# Header.net
KiCad netlist of a schematic drawn in Altium Designer
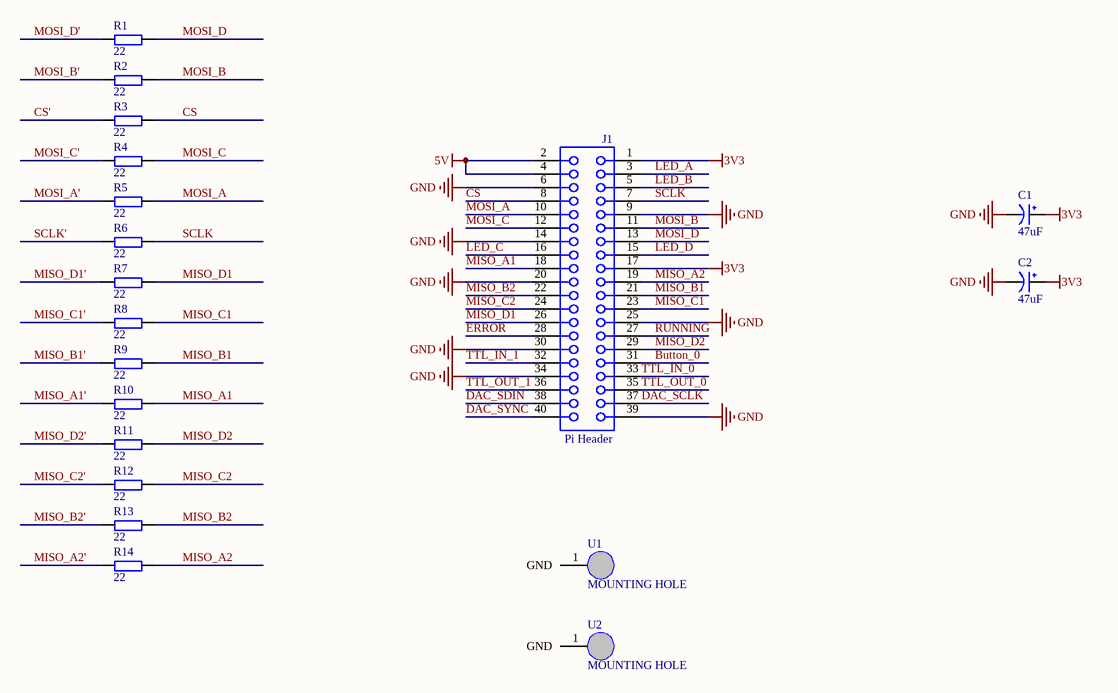
[diagram p0: Header.SchDoc]

(export (version "E")
  (design (tool "Eeschema 10.0.6"))
  (components
    (comp (ref "C1") (value "47uF") (footprint "CD A(3216)") (libsource (lib "ZYNQ_开发板") (part "CAP")))
    (comp (ref "C2") (value "47uF") (footprint "CD A(3216)") (libsource (lib "ZYNQ_开发板") (part "CAP")))
    (comp (ref "J1")
      (value "Pi Header")
      (footprint "61304021821")
      (description "THT Vertical Socket Header WR-PHD, Pitch 2.54 mm, Dual Row, 40 pins")
      (libsource (lib "Altium Content Vault") (part "Header_Female_2R_40P"))
    )
    (comp (ref "R1") (value "22") (footprint "R 0402_L") (libsource (lib "ZYNQ_开发板") (part "R")))
    (comp (ref "R2") (value "22") (footprint "R 0402_L") (libsource (lib "ZYNQ_开发板") (part "R")))
    (comp (ref "R3") (value "22") (footprint "R 0402_L") (libsource (lib "ZYNQ_开发板") (part "R")))
    (comp (ref "R4") (value "22") (footprint "R 0402_L") (libsource (lib "ZYNQ_开发板") (part "R")))
    (comp (ref "R5") (value "22") (footprint "R 0402_L") (libsource (lib "ZYNQ_开发板") (part "R")))
    (comp (ref "R6") (value "22") (footprint "R 0402_L") (libsource (lib "ZYNQ_开发板") (part "R")))
    (comp (ref "R7") (value "22") (footprint "R 0402_L") (libsource (lib "ZYNQ_开发板") (part "R")))
    (comp (ref "R8") (value "22") (footprint "R 0402_L") (libsource (lib "ZYNQ_开发板") (part "R")))
    (comp (ref "R9") (value "22") (footprint "R 0402_L") (libsource (lib "ZYNQ_开发板") (part "R")))
    (comp (ref "R10") (value "22") (footprint "R 0402_L") (libsource (lib "ZYNQ_开发板") (part "R")))
    (comp (ref "R11") (value "22") (footprint "R 0402_L") (libsource (lib "ZYNQ_开发板") (part "R")))
    (comp (ref "R12") (value "22") (footprint "R 0402_L") (libsource (lib "ZYNQ_开发板") (part "R")))
    (comp (ref "R13") (value "22") (footprint "R 0402_L") (libsource (lib "ZYNQ_开发板") (part "R")))
    (comp (ref "R14") (value "22") (footprint "R 0402_L") (libsource (lib "ZYNQ_开发板") (part "R")))
    (comp (ref "U1")
      (value "MOUNTING HOLE")
      (footprint "mounting_hole")
      (fields (field (name "PART NUMBER") "VJ0805Y105KXQRW1BC") (field (name "MANUFACTURER") "Vitramon"))
      (libsource (lib "Mounting_Hole") (part "MountingHole"))
    )
    (comp (ref "U2")
      (value "MOUNTING HOLE")
      (footprint "mounting_hole")
      (fields (field (name "PART NUMBER") "VJ0805Y105KXQRW1BC") (field (name "MANUFACTURER") "Vitramon"))
      (libsource (lib "Mounting_Hole") (part "MountingHole"))
    )
  )
  (nets
    (net (code "1") (name "/Button_0") (class "Default")
      (node (ref "J1") (pin "31") (pinfunction "31_31") (pintype "passive"))
    )
    (net (code "2") (name "/CS") (class "Default")
      (node (ref "J1") (pin "8") (pinfunction "8_8") (pintype "passive"))
      (node (ref "R3") (pin "2") (pintype "passive"))
    )
    (net (code "3") (name "/CS'") (class "Default") (node (ref "R3") (pin "1") (pintype "passive")))
    (net (code "4") (name "/DAC_SCLK") (class "Default")
      (node (ref "J1") (pin "37") (pinfunction "37_37") (pintype "passive"))
    )
    (net (code "5") (name "/DAC_SDIN") (class "Default")
      (node (ref "J1") (pin "38") (pinfunction "38_38") (pintype "passive"))
    )
    (net (code "6") (name "/DAC_SYNC") (class "Default")
      (node (ref "J1") (pin "40") (pinfunction "40_40") (pintype "passive"))
    )
    (net (code "7") (name "/ERROR") (class "Default")
      (node (ref "J1") (pin "28") (pinfunction "28_28") (pintype "passive"))
    )
    (net (code "8") (name "/LED_A") (class "Default")
      (node (ref "J1") (pin "3") (pinfunction "3_3") (pintype "passive"))
    )
    (net (code "9") (name "/LED_B") (class "Default")
      (node (ref "J1") (pin "5") (pinfunction "5_5") (pintype "passive"))
    )
    (net (code "10") (name "/LED_C") (class "Default")
      (node (ref "J1") (pin "16") (pinfunction "16_16") (pintype "passive"))
    )
    (net (code "11") (name "/LED_D") (class "Default")
      (node (ref "J1") (pin "15") (pinfunction "15_15") (pintype "passive"))
    )
    (net (code "12") (name "/MISO_A1") (class "Default")
      (node (ref "J1") (pin "18") (pinfunction "18_18") (pintype "passive"))
      (node (ref "R10") (pin "2") (pintype "passive"))
    )
    (net (code "13") (name "/MISO_A1'") (class "Default") (node (ref "R10") (pin "1") (pintype "passive")))
    (net (code "14") (name "/MISO_A2") (class "Default")
      (node (ref "J1") (pin "19") (pinfunction "19_19") (pintype "passive"))
      (node (ref "R14") (pin "2") (pintype "passive"))
    )
    (net (code "15") (name "/MISO_A2'") (class "Default") (node (ref "R14") (pin "1") (pintype "passive")))
    (net (code "16") (name "/MISO_B1") (class "Default")
      (node (ref "J1") (pin "21") (pinfunction "21_21") (pintype "passive"))
      (node (ref "R9") (pin "2") (pintype "passive"))
    )
    (net (code "17") (name "/MISO_B1'") (class "Default") (node (ref "R9") (pin "1") (pintype "passive")))
    (net (code "18") (name "/MISO_B2") (class "Default")
      (node (ref "J1") (pin "22") (pinfunction "22_22") (pintype "passive"))
      (node (ref "R13") (pin "2") (pintype "passive"))
    )
    (net (code "19") (name "/MISO_B2'") (class "Default") (node (ref "R13") (pin "1") (pintype "passive")))
    (net (code "20") (name "/MISO_C1") (class "Default")
      (node (ref "J1") (pin "23") (pinfunction "23_23") (pintype "passive"))
      (node (ref "R8") (pin "2") (pintype "passive"))
    )
    (net (code "21") (name "/MISO_C1'") (class "Default") (node (ref "R8") (pin "1") (pintype "passive")))
    (net (code "22") (name "/MISO_C2") (class "Default")
      (node (ref "J1") (pin "24") (pinfunction "24_24") (pintype "passive"))
      (node (ref "R12") (pin "2") (pintype "passive"))
    )
    (net (code "23") (name "/MISO_C2'") (class "Default") (node (ref "R12") (pin "1") (pintype "passive")))
    (net (code "24") (name "/MISO_D1") (class "Default")
      (node (ref "J1") (pin "26") (pinfunction "26_26") (pintype "passive"))
      (node (ref "R7") (pin "2") (pintype "passive"))
    )
    (net (code "25") (name "/MISO_D1'") (class "Default") (node (ref "R7") (pin "1") (pintype "passive")))
    (net (code "26") (name "/MISO_D2") (class "Default")
      (node (ref "J1") (pin "29") (pinfunction "29_29") (pintype "passive"))
      (node (ref "R11") (pin "2") (pintype "passive"))
    )
    (net (code "27") (name "/MISO_D2'") (class "Default") (node (ref "R11") (pin "1") (pintype "passive")))
    (net (code "28") (name "/MOSI_A") (class "Default")
      (node (ref "J1") (pin "10") (pinfunction "10_10") (pintype "passive"))
      (node (ref "R5") (pin "2") (pintype "passive"))
    )
    (net (code "29") (name "/MOSI_A'") (class "Default") (node (ref "R5") (pin "1") (pintype "passive")))
    (net (code "30") (name "/MOSI_B") (class "Default")
      (node (ref "J1") (pin "11") (pinfunction "11_11") (pintype "passive"))
      (node (ref "R2") (pin "2") (pintype "passive"))
    )
    (net (code "31") (name "/MOSI_B'") (class "Default") (node (ref "R2") (pin "1") (pintype "passive")))
    (net (code "32") (name "/MOSI_C") (class "Default")
      (node (ref "J1") (pin "12") (pinfunction "12_12") (pintype "passive"))
      (node (ref "R4") (pin "2") (pintype "passive"))
    )
    (net (code "33") (name "/MOSI_C'") (class "Default") (node (ref "R4") (pin "1") (pintype "passive")))
    (net (code "34") (name "/MOSI_D") (class "Default")
      (node (ref "J1") (pin "13") (pinfunction "13_13") (pintype "passive"))
      (node (ref "R1") (pin "2") (pintype "passive"))
    )
    (net (code "35") (name "/MOSI_D'") (class "Default") (node (ref "R1") (pin "1") (pintype "passive")))
    (net (code "36") (name "/RUNNING") (class "Default")
      (node (ref "J1") (pin "27") (pinfunction "27_27") (pintype "passive"))
    )
    (net (code "37") (name "/SCLK") (class "Default")
      (node (ref "J1") (pin "7") (pinfunction "7_7") (pintype "passive"))
      (node (ref "R6") (pin "2") (pintype "passive"))
    )
    (net (code "38") (name "/SCLK'") (class "Default") (node (ref "R6") (pin "1") (pintype "passive")))
    (net (code "39") (name "/TTL_IN_0") (class "Default")
      (node (ref "J1") (pin "33") (pinfunction "33_33") (pintype "passive"))
    )
    (net (code "40") (name "/TTL_IN_1") (class "Default")
      (node (ref "J1") (pin "32") (pinfunction "32_32") (pintype "passive"))
    )
    (net (code "41") (name "/TTL_OUT_0") (class "Default")
      (node (ref "J1") (pin "35") (pinfunction "35_35") (pintype "passive"))
    )
    (net (code "42") (name "/TTL_OUT_1") (class "Default")
      (node (ref "J1") (pin "36") (pinfunction "36_36") (pintype "passive"))
    )
    (net (code "43") (name "3V3") (class "Default")
      (node (ref "C1") (pin "1") (pinfunction "VCC_1") (pintype "passive"))
      (node (ref "C2") (pin "1") (pinfunction "VCC_1") (pintype "passive"))
      (node (ref "J1") (pin "1") (pinfunction "1_1") (pintype "passive"))
      (node (ref "J1") (pin "17") (pinfunction "17_17") (pintype "passive"))
    )
    (net (code "44") (name "5V") (class "Default")
      (node (ref "J1") (pin "2") (pinfunction "2_2") (pintype "passive"))
      (node (ref "J1") (pin "4") (pinfunction "4_4") (pintype "passive"))
    )
    (net (code "45") (name "GND") (class "Default")
      (node (ref "C1") (pin "2") (pinfunction "GND_2") (pintype "passive"))
      (node (ref "C2") (pin "2") (pinfunction "GND_2") (pintype "passive"))
      (node (ref "J1") (pin "14") (pinfunction "14_14") (pintype "passive"))
      (node (ref "J1") (pin "20") (pinfunction "20_20") (pintype "passive"))
      (node (ref "J1") (pin "25") (pinfunction "25_25") (pintype "passive"))
      (node (ref "J1") (pin "30") (pinfunction "30_30") (pintype "passive"))
      (node (ref "J1") (pin "34") (pinfunction "34_34") (pintype "passive"))
      (node (ref "J1") (pin "39") (pinfunction "39_39") (pintype "passive"))
      (node (ref "J1") (pin "6") (pinfunction "6_6") (pintype "passive"))
      (node (ref "J1") (pin "9") (pinfunction "9_9") (pintype "passive"))
    )
    (net (code "46") (name "unconnected-(U1-GND-Pad1)") (class "Default")
      (node (ref "U1") (pin "1") (pinfunction "GND_1") (pintype "passive"))
    )
    (net (code "47") (name "unconnected-(U2-GND-Pad1)") (class "Default")
      (node (ref "U2") (pin "1") (pinfunction "GND_1") (pintype "passive"))
    )
  )
)
